# Flashlight.net
KiCad netlist of a schematic drawn in EAGLE
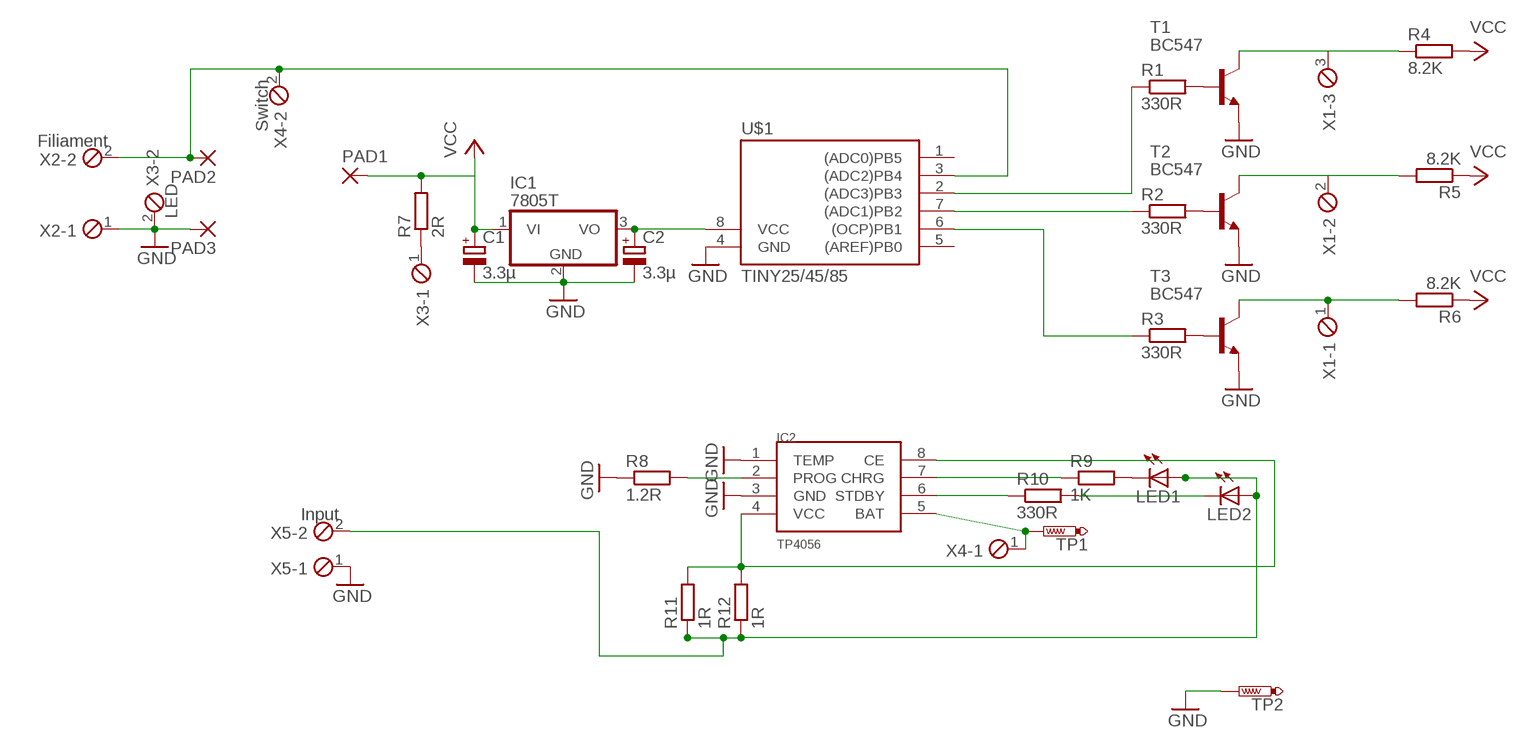
[diagram p0: schematic, sheet 1]

(export (version "E")
  (design (tool "Eeschema 10.0.6"))
  (components
    (comp (ref "C1")
      (value "3.3µ")
      (footprint "eagle-import:E2,5-6")
      (libsource (lib "eagle-import") (part "CPOL-EUE2.5-6"))
    )
    (comp (ref "C2")
      (value "3.3µ")
      (footprint "eagle-import:E2,5-6")
      (libsource (lib "eagle-import") (part "CPOL-EUE2.5-6"))
    )
    (comp (ref "IC1")
      (value "7805T")
      (footprint "eagle-import:TO220H")
      (libsource (lib "eagle-import") (part "78T05"))
    )
    (comp (ref "IC2")
      (value "TP4056")
      (footprint "eagle-import:SOP-8")
      (libsource (lib "eagle-import") (part "TP4056"))
    )
    (comp (ref "LED1")
      (value "LED3MM")
      (footprint "eagle-import:LED3MM")
      (libsource (lib "eagle-import") (part "LED3MM"))
    )
    (comp (ref "LED2")
      (value "LED3MM")
      (footprint "eagle-import:LED3MM")
      (libsource (lib "eagle-import") (part "LED3MM"))
    )
    (comp (ref "PAD1")
      (value "3,81/1,3")
      (footprint "eagle-import:3,81_1,3")
      (libsource (lib "eagle-import") (part "3,81/1,3"))
    )
    (comp (ref "PAD2")
      (value "3,81/1,3")
      (footprint "eagle-import:3,81_1,3")
      (libsource (lib "eagle-import") (part "3,81/1,3"))
    )
    (comp (ref "PAD3")
      (value "3,81/1,3")
      (footprint "eagle-import:3,81_1,3")
      (libsource (lib "eagle-import") (part "3,81/1,3"))
    )
    (comp (ref "R1")
      (value "330R")
      (footprint "eagle-import:R1206")
      (libsource (lib "eagle-import") (part "R-EU_R1206"))
    )
    (comp (ref "R2")
      (value "330R")
      (footprint "eagle-import:R1206")
      (libsource (lib "eagle-import") (part "R-EU_R1206"))
    )
    (comp (ref "R3")
      (value "330R")
      (footprint "eagle-import:R1206")
      (libsource (lib "eagle-import") (part "R-EU_R1206"))
    )
    (comp (ref "R4")
      (value "8.2K")
      (footprint "eagle-import:R1206")
      (libsource (lib "eagle-import") (part "R-EU_R1206"))
    )
    (comp (ref "R5")
      (value "8.2K")
      (footprint "eagle-import:R1206")
      (libsource (lib "eagle-import") (part "R-EU_R1206"))
    )
    (comp (ref "R6")
      (value "8.2K")
      (footprint "eagle-import:R1206")
      (libsource (lib "eagle-import") (part "R-EU_R1206"))
    )
    (comp (ref "R7")
      (value "2R")
      (footprint "eagle-import:0411_12")
      (libsource (lib "eagle-import") (part "R-EU_0411/12"))
    )
    (comp (ref "R8")
      (value "1.2R")
      (footprint "eagle-import:M1206")
      (libsource (lib "eagle-import") (part "R-EU_M1206"))
    )
    (comp (ref "R9")
      (value "1K")
      (footprint "eagle-import:M1206")
      (libsource (lib "eagle-import") (part "R-EU_M1206"))
    )
    (comp (ref "R10")
      (value "330R")
      (footprint "eagle-import:M1206")
      (libsource (lib "eagle-import") (part "R-EU_M1206"))
    )
    (comp (ref "R11")
      (value "1R")
      (footprint "eagle-import:M1206")
      (libsource (lib "eagle-import") (part "R-EU_M1206"))
    )
    (comp (ref "R12")
      (value "1R")
      (footprint "eagle-import:M1206")
      (libsource (lib "eagle-import") (part "R-EU_M1206"))
    )
    (comp (ref "T1")
      (value "BC547")
      (footprint "eagle-import:TO92")
      (libsource (lib "eagle-import") (part "BC547"))
    )
    (comp (ref "T2")
      (value "BC547")
      (footprint "eagle-import:TO92")
      (libsource (lib "eagle-import") (part "BC547"))
    )
    (comp (ref "T3")
      (value "BC547")
      (footprint "eagle-import:TO92")
      (libsource (lib "eagle-import") (part "BC547"))
    )
    (comp (ref "TP1")
      (value "PTR1PAD1-13")
      (footprint "eagle-import:P1-13")
      (libsource (lib "eagle-import") (part "PTR1PAD1-13"))
    )
    (comp (ref "TP2")
      (value "PTR1PAD1-13")
      (footprint "eagle-import:P1-13")
      (libsource (lib "eagle-import") (part "PTR1PAD1-13"))
    )
    (comp (ref "U$1")
      (value "TINY25/45/85")
      (footprint "eagle-import:DIL08")
      (libsource (lib "eagle-import") (part "TINY25/45/85"))
    )
    (comp (ref "X1")
      (value "MPT3")
      (footprint "eagle-import:3POL254")
      (libsource (lib "eagle-import") (part "MPT3"))
    )
    (comp (ref "X2")
      (value "Filiament")
      (footprint "eagle-import:2POL254")
      (libsource (lib "eagle-import") (part "MPT2"))
    )
    (comp (ref "X3")
      (value "LED")
      (footprint "eagle-import:2POL254")
      (libsource (lib "eagle-import") (part "MPT2"))
    )
    (comp (ref "X4")
      (value "Switch")
      (footprint "eagle-import:2POL254")
      (libsource (lib "eagle-import") (part "MPT2"))
    )
    (comp (ref "X5")
      (value "Input")
      (footprint "eagle-import:2POL254")
      (libsource (lib "eagle-import") (part "MPT2"))
    )
  )
  (nets
    (net (code "1") (name "GND") (class "Default")
      (node (ref "C1") (pin "-") (pinfunction "-_-") (pintype "passive"))
      (node (ref "C2") (pin "-") (pinfunction "-_-") (pintype "passive"))
      (node (ref "IC1") (pin "2") (pinfunction "GND_2") (pintype "passive"))
      (node (ref "IC2") (pin "1") (pinfunction "TEMP_1") (pintype "bidirectional"))
      (node (ref "IC2") (pin "3") (pinfunction "GND_3") (pintype "bidirectional"))
      (node (ref "PAD3") (pin "1") (pinfunction "P_1") (pintype "passive"))
      (node (ref "R8") (pin "1") (pinfunction "1_1") (pintype "passive"))
      (node (ref "T1") (pin "1") (pinfunction "E_1") (pintype "passive"))
      (node (ref "T2") (pin "1") (pinfunction "E_1") (pintype "passive"))
      (node (ref "T3") (pin "1") (pinfunction "E_1") (pintype "passive"))
      (node (ref "TP2") (pin "TP") (pinfunction "TP_TP") (pintype "input"))
      (node (ref "U$1") (pin "4") (pinfunction "GND_4") (pintype "power_in"))
      (node (ref "X2") (pin "1") (pinfunction "1_1") (pintype "passive"))
      (node (ref "X3") (pin "2") (pinfunction "1_2") (pintype "passive"))
      (node (ref "X5") (pin "1") (pinfunction "1_1") (pintype "passive"))
    )
    (net (code "2") (name "Net-(IC1-VO)") (class "Default")
      (node (ref "C2") (pin "+") (pinfunction "+_+") (pintype "passive"))
      (node (ref "IC1") (pin "3") (pinfunction "VO_3") (pintype "passive"))
      (node (ref "U$1") (pin "8") (pinfunction "VCC_8") (pintype "power_in"))
    )
    (net (code "3") (name "Net-(IC2-BAT)") (class "Default")
      (node (ref "IC2") (pin "5") (pinfunction "BAT_5") (pintype "bidirectional"))
      (node (ref "TP1") (pin "TP") (pinfunction "TP_TP") (pintype "input"))
      (node (ref "X4") (pin "1") (pinfunction "1_1") (pintype "passive"))
    )
    (net (code "4") (name "Net-(IC2-CE)") (class "Default")
      (node (ref "IC2") (pin "4") (pinfunction "VCC_4") (pintype "bidirectional"))
      (node (ref "IC2") (pin "8") (pinfunction "CE_8") (pintype "bidirectional"))
      (node (ref "R11") (pin "2") (pinfunction "2_2") (pintype "passive"))
      (node (ref "R12") (pin "2") (pinfunction "2_2") (pintype "passive"))
    )
    (net (code "5") (name "Net-(IC2-CHRG)") (class "Default")
      (node (ref "IC2") (pin "7") (pinfunction "CHRG_7") (pintype "bidirectional"))
      (node (ref "R9") (pin "1") (pinfunction "1_1") (pintype "passive"))
    )
    (net (code "6") (name "Net-(IC2-PROG)") (class "Default")
      (node (ref "IC2") (pin "2") (pinfunction "PROG_2") (pintype "bidirectional"))
      (node (ref "R8") (pin "2") (pinfunction "2_2") (pintype "passive"))
    )
    (net (code "7") (name "Net-(IC2-STDBY)") (class "Default")
      (node (ref "IC2") (pin "6") (pinfunction "STDBY_6") (pintype "bidirectional"))
      (node (ref "R10") (pin "1") (pinfunction "1_1") (pintype "passive"))
    )
    (net (code "8") (name "Net-(LED1-C)") (class "Default")
      (node (ref "LED1") (pin "K") (pinfunction "C_K") (pintype "passive"))
      (node (ref "R9") (pin "2") (pinfunction "2_2") (pintype "passive"))
    )
    (net (code "9") (name "Net-(LED2-C)") (class "Default")
      (node (ref "LED2") (pin "K") (pinfunction "C_K") (pintype "passive"))
      (node (ref "R10") (pin "2") (pinfunction "2_2") (pintype "passive"))
    )
    (net (code "10") (name "Net-(PAD2-P)") (class "Default")
      (node (ref "PAD2") (pin "1") (pinfunction "P_1") (pintype "passive"))
      (node (ref "U$1") (pin "3") (pinfunction "(ADC2)PB4_3") (pintype "bidirectional"))
      (node (ref "X2") (pin "2") (pinfunction "1_2") (pintype "passive"))
      (node (ref "X4") (pin "2") (pinfunction "1_2") (pintype "passive"))
    )
    (net (code "11") (name "Net-(R7-Pad1)") (class "Default")
      (node (ref "R7") (pin "1") (pinfunction "1_1") (pintype "passive"))
      (node (ref "X3") (pin "1") (pinfunction "1_1") (pintype "passive"))
    )
    (net (code "12") (name "Net-(T1-B)") (class "Default")
      (node (ref "R1") (pin "2") (pinfunction "2_2") (pintype "passive"))
      (node (ref "T1") (pin "2") (pinfunction "B_2") (pintype "passive"))
    )
    (net (code "13") (name "Net-(T1-C)") (class "Default")
      (node (ref "R4") (pin "1") (pinfunction "1_1") (pintype "passive"))
      (node (ref "T1") (pin "3") (pinfunction "C_3") (pintype "passive"))
      (node (ref "X1") (pin "3") (pinfunction "1_3") (pintype "passive"))
    )
    (net (code "14") (name "Net-(T2-B)") (class "Default")
      (node (ref "R2") (pin "2") (pinfunction "2_2") (pintype "passive"))
      (node (ref "T2") (pin "2") (pinfunction "B_2") (pintype "passive"))
    )
    (net (code "15") (name "Net-(T2-C)") (class "Default")
      (node (ref "R5") (pin "2") (pinfunction "2_2") (pintype "passive"))
      (node (ref "T2") (pin "3") (pinfunction "C_3") (pintype "passive"))
      (node (ref "X1") (pin "2") (pinfunction "1_2") (pintype "passive"))
    )
    (net (code "16") (name "Net-(T3-B)") (class "Default")
      (node (ref "R3") (pin "2") (pinfunction "2_2") (pintype "passive"))
      (node (ref "T3") (pin "2") (pinfunction "B_2") (pintype "passive"))
    )
    (net (code "17") (name "Net-(T3-C)") (class "Default")
      (node (ref "R6") (pin "2") (pinfunction "2_2") (pintype "passive"))
      (node (ref "T3") (pin "3") (pinfunction "C_3") (pintype "passive"))
      (node (ref "X1") (pin "1") (pinfunction "1_1") (pintype "passive"))
    )
    (net (code "18") (name "Net-(U$1-(ADC1)PB2)") (class "Default")
      (node (ref "R2") (pin "1") (pinfunction "1_1") (pintype "passive"))
      (node (ref "U$1") (pin "7") (pinfunction "(ADC1)PB2_7") (pintype "bidirectional"))
    )
    (net (code "19") (name "Net-(U$1-(ADC3)PB3)") (class "Default")
      (node (ref "R1") (pin "1") (pinfunction "1_1") (pintype "passive"))
      (node (ref "U$1") (pin "2") (pinfunction "(ADC3)PB3_2") (pintype "bidirectional"))
    )
    (net (code "20") (name "Net-(U$1-(OCP)PB1)") (class "Default")
      (node (ref "R3") (pin "1") (pinfunction "1_1") (pintype "passive"))
      (node (ref "U$1") (pin "6") (pinfunction "(OCP)PB1_6") (pintype "bidirectional"))
    )
    (net (code "21") (name "Net-(X5B-1)") (class "Default")
      (node (ref "LED1") (pin "A") (pinfunction "A_A") (pintype "passive"))
      (node (ref "LED2") (pin "A") (pinfunction "A_A") (pintype "passive"))
      (node (ref "R11") (pin "1") (pinfunction "1_1") (pintype "passive"))
      (node (ref "R12") (pin "1") (pinfunction "1_1") (pintype "passive"))
      (node (ref "X5") (pin "2") (pinfunction "1_2") (pintype "passive"))
    )
    (net (code "22") (name "VCC") (class "Default")
      (node (ref "C1") (pin "+") (pinfunction "+_+") (pintype "passive"))
      (node (ref "IC1") (pin "1") (pinfunction "VI_1") (pintype "input"))
      (node (ref "PAD1") (pin "1") (pinfunction "P_1") (pintype "passive"))
      (node (ref "R4") (pin "2") (pinfunction "2_2") (pintype "passive"))
      (node (ref "R5") (pin "1") (pinfunction "1_1") (pintype "passive"))
      (node (ref "R6") (pin "1") (pinfunction "1_1") (pintype "passive"))
      (node (ref "R7") (pin "2") (pinfunction "2_2") (pintype "passive"))
    )
    (net (code "23") (name "unconnected-(U$1-(ADC0)PB5-Pad1)") (class "Default")
      (node (ref "U$1") (pin "1") (pinfunction "(ADC0)PB5_1") (pintype "bidirectional"))
    )
    (net (code "24") (name "unconnected-(U$1-(AREF)PB0-Pad5)") (class "Default")
      (node (ref "U$1") (pin "5") (pinfunction "(AREF)PB0_5") (pintype "bidirectional"))
    )
  )
)
